# Sigfox_Featherwing-RP_SMA.net
KiCad netlist of a schematic drawn in EAGLE
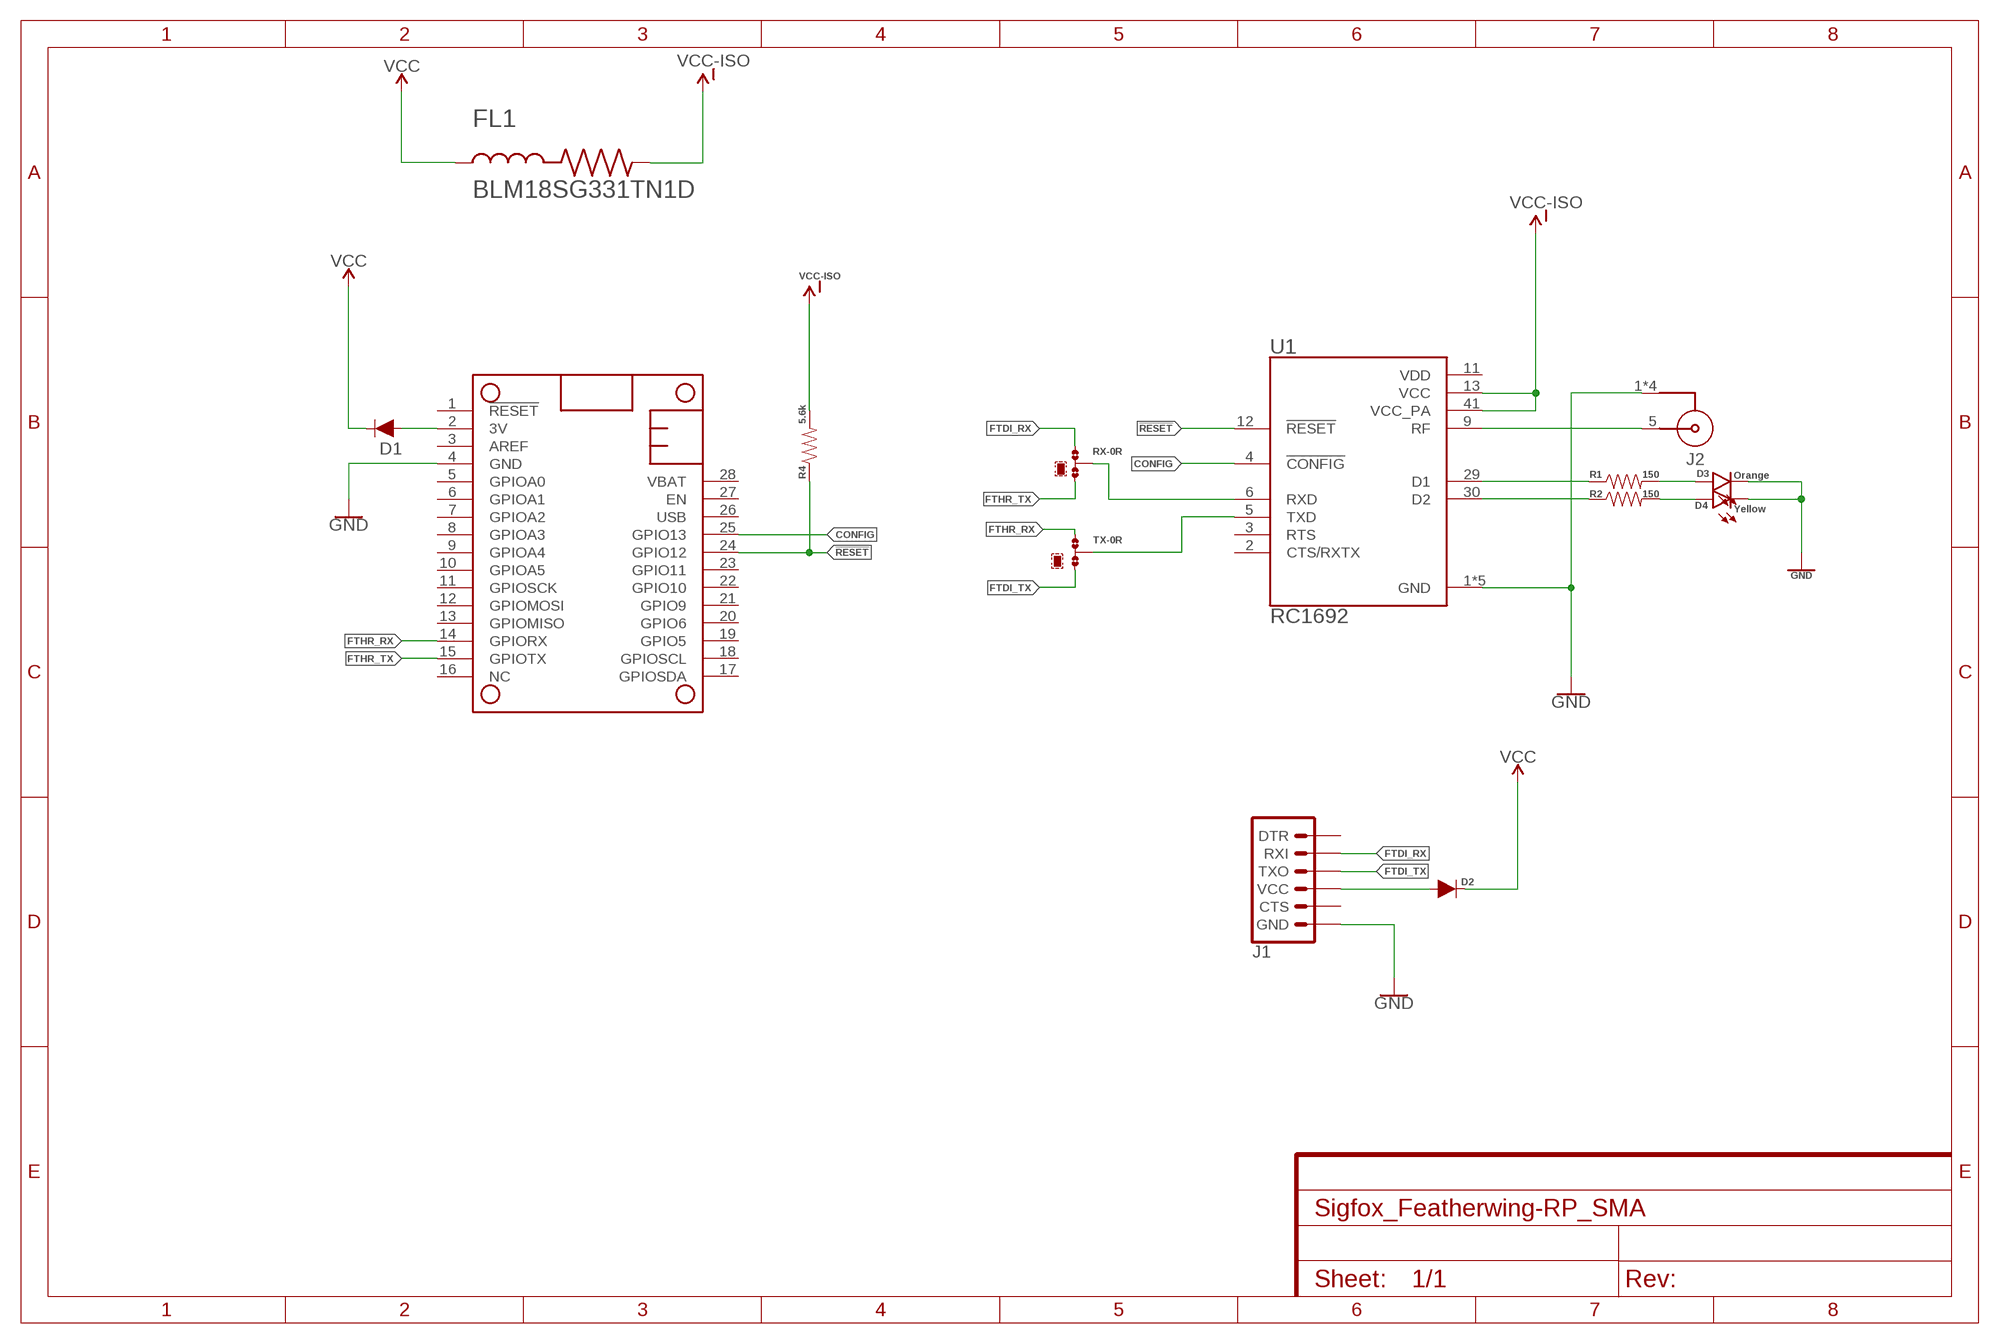
[diagram p0: schematic, sheet 1]

(export (version "E")
  (design (tool "Eeschema 10.0.6"))
  (components
    (comp (ref "D1")
      (value "250mA/100V")
      (footprint "eagle-import:SOD-323")
      (libsource (lib "eagle-import") (part "DIODE-BAS16J"))
    )
    (comp (ref "D2")
      (value "250mA/100V")
      (footprint "eagle-import:SOD-323")
      (libsource (lib "eagle-import") (part "DIODE-BAS16J"))
    )
    (comp (ref "D3")
      (value "Orange")
      (footprint "eagle-import:LED-0603")
      (libsource (lib "eagle-import") (part "LED-YELLOW0603"))
    )
    (comp (ref "D4")
      (value "Yellow")
      (footprint "eagle-import:LED-0603")
      (libsource (lib "eagle-import") (part "LED-YELLOW0603"))
    )
    (comp (ref "FL1")
      (value "BLM18SG331TN1D")
      (footprint "eagle-import:BEADC1608X65N")
      (fields (field (name "MF") "Murata Electronics"))
      (libsource (lib "eagle-import") (part "BLM18SG331TN1D"))
    )
    (comp (ref "J1")
      (value "6_PIN_SERIAL_TARGETSILK")
      (footprint "eagle-import:6_PIN_SERIAL_TARGET_SIDE_W_SILK")
      (libsource (lib "eagle-import") (part "6_PIN_SERIAL_TARGETSILK"))
    )
    (comp (ref "J2")
      (value "63012002124503")
      (footprint "eagle-import:63012002124503")
      (fields
        (field (name "DIGI-KEY_PART_NUMBER") "732-13860-ND")
        (field (name "MF") "Wurth Electronics Inc.")
      )
      (libsource (lib "eagle-import") (part "63012002124503"))
    )
    (comp (ref "MS1")
      (value "FEATHERWING")
      (footprint "eagle-import:FEATHERWING")
      (libsource (lib "eagle-import") (part "FEATHERWING"))
    )
    (comp (ref "R1")
      (value "150")
      (footprint "eagle-import:0603")
      (libsource (lib "eagle-import") (part "150OHM-0603-1/10W-1%"))
    )
    (comp (ref "R2")
      (value "150")
      (footprint "eagle-import:0603")
      (libsource (lib "eagle-import") (part "150OHM-0603-1/10W-1%"))
    )
    (comp (ref "R4")
      (value "5.6k")
      (footprint "eagle-import:0603")
      (libsource (lib "eagle-import") (part "5.6KOHM-0603-1/10W-1%"))
    )
    (comp (ref "RX")
      (value "0R-JUMPB")
      (footprint "eagle-import:B0R-JMP")
      (libsource (lib "eagle-import") (part "0R-JUMPB"))
    )
    (comp (ref "TX")
      (value "0R-JUMPB")
      (footprint "eagle-import:B0R-JMP")
      (libsource (lib "eagle-import") (part "0R-JUMPB"))
    )
    (comp (ref "U1")
      (value "RC1692")
      (footprint "eagle-import:MODULE_RC1682-SIG")
      (fields (field (name "MF") "Radiocrafts AS") (field (name "MP") "RC1682-SIG"))
      (libsource (lib "eagle-import") (part "RC1692"))
    )
  )
  (nets
    (net (code "1") (name "/USB") (class "Default")
      (node (ref "MS1") (pin "26") (pinfunction "USB_26") (pintype "power_in"))
    )
    (net (code "2") (name "/VBAT") (class "Default")
      (node (ref "MS1") (pin "28") (pinfunction "VBAT_28") (pintype "power_in"))
    )
    (net (code "3") (name "/VDD") (class "Default")
      (node (ref "U1") (pin "11") (pinfunction "VDD_11") (pintype "power_in"))
    )
    (net (code "4") (name "/~{RESET}") (class "Default")
      (node (ref "MS1") (pin "24") (pinfunction "GPIO12_24") (pintype "bidirectional"))
      (node (ref "R4") (pin "1") (pinfunction "1_1") (pintype "passive"))
      (node (ref "U1") (pin "12") (pinfunction "~{RESET}_12") (pintype "input"))
    )
    (net (code "5") (name "CONFIG") (class "Default")
      (node (ref "MS1") (pin "25") (pinfunction "GPIO13_25") (pintype "bidirectional"))
      (node (ref "U1") (pin "4") (pinfunction "~{CONFIG}_4") (pintype "input"))
    )
    (net (code "6") (name "FTDI_RX") (class "Default")
      (node (ref "J1") (pin "P$3") (pinfunction "RXI_P$3") (pintype "passive"))
      (node (ref "RX") (pin "1") (pinfunction "1_1") (pintype "passive"))
    )
    (net (code "7") (name "FTDI_TX") (class "Default")
      (node (ref "J1") (pin "P$2") (pinfunction "TXO_P$2") (pintype "passive"))
      (node (ref "TX") (pin "3") (pinfunction "3_3") (pintype "passive"))
    )
    (net (code "8") (name "FTHR_RX") (class "Default")
      (node (ref "MS1") (pin "14") (pinfunction "GPIORX_14") (pintype "bidirectional"))
      (node (ref "TX") (pin "1") (pinfunction "1_1") (pintype "passive"))
    )
    (net (code "9") (name "FTHR_TX") (class "Default")
      (node (ref "MS1") (pin "15") (pinfunction "GPIOTX_15") (pintype "bidirectional"))
      (node (ref "RX") (pin "3") (pinfunction "3_3") (pintype "passive"))
    )
    (net (code "10") (name "GND") (class "Default")
      (node (ref "D3") (pin "C") (pinfunction "C_C") (pintype "passive"))
      (node (ref "D4") (pin "C") (pinfunction "C_C") (pintype "passive"))
      (node (ref "J1") (pin "P$6") (pinfunction "GND_P$6") (pintype "passive"))
      (node (ref "J2") (pin "1") (pinfunction "2_1") (pintype "passive"))
      (node (ref "J2") (pin "2") (pinfunction "2_2") (pintype "passive"))
      (node (ref "J2") (pin "3") (pinfunction "2_3") (pintype "passive"))
      (node (ref "J2") (pin "4") (pinfunction "2_4") (pintype "passive"))
      (node (ref "MS1") (pin "4") (pinfunction "GND_4") (pintype "power_in"))
      (node (ref "U1") (pin "1") (pinfunction "GND_1") (pintype "power_in"))
      (node (ref "U1") (pin "10") (pinfunction "GND_10") (pintype "power_in"))
      (node (ref "U1") (pin "14") (pinfunction "GND_14") (pintype "power_in"))
      (node (ref "U1") (pin "7") (pinfunction "GND_7") (pintype "power_in"))
      (node (ref "U1") (pin "8") (pinfunction "GND_8") (pintype "power_in"))
    )
    (net (code "11") (name "Net-(D3-PadA)") (class "Default")
      (node (ref "D3") (pin "A") (pinfunction "A_A") (pintype "passive"))
      (node (ref "R1") (pin "2") (pinfunction "2_2") (pintype "passive"))
    )
    (net (code "12") (name "Net-(D4-PadA)") (class "Default")
      (node (ref "D4") (pin "A") (pinfunction "A_A") (pintype "passive"))
      (node (ref "R2") (pin "2") (pinfunction "2_2") (pintype "passive"))
    )
    (net (code "13") (name "Net-(J1-VCC)") (class "Default")
      (node (ref "D2") (pin "A") (pinfunction "A_A") (pintype "passive"))
      (node (ref "J1") (pin "P$4") (pinfunction "VCC_P$4") (pintype "passive"))
    )
    (net (code "14") (name "Net-(J2-1)") (class "Default")
      (node (ref "J2") (pin "5") (pinfunction "1_5") (pintype "passive"))
      (node (ref "U1") (pin "9") (pinfunction "RF_9") (pintype "bidirectional"))
    )
    (net (code "15") (name "Net-(MS1-3V)") (class "Default")
      (node (ref "D1") (pin "A") (pinfunction "A_A") (pintype "passive"))
      (node (ref "MS1") (pin "2") (pinfunction "3V_2") (pintype "power_in"))
    )
    (net (code "16") (name "Net-(U1-D1)") (class "Default")
      (node (ref "R1") (pin "1") (pinfunction "1_1") (pintype "passive"))
      (node (ref "U1") (pin "29") (pinfunction "D1_29") (pintype "bidirectional"))
    )
    (net (code "17") (name "Net-(U1-D2)") (class "Default")
      (node (ref "R2") (pin "1") (pinfunction "1_1") (pintype "passive"))
      (node (ref "U1") (pin "30") (pinfunction "D2_30") (pintype "bidirectional"))
    )
    (net (code "18") (name "Net-(U1-RXD)") (class "Default")
      (node (ref "RX") (pin "2") (pinfunction "2_2") (pintype "passive"))
      (node (ref "U1") (pin "6") (pinfunction "RXD_6") (pintype "input"))
    )
    (net (code "19") (name "Net-(U1-TXD)") (class "Default")
      (node (ref "TX") (pin "2") (pinfunction "2_2") (pintype "passive"))
      (node (ref "U1") (pin "5") (pinfunction "TXD_5") (pintype "output"))
    )
    (net (code "20") (name "VCC") (class "Default")
      (node (ref "D1") (pin "C") (pinfunction "C_C") (pintype "passive"))
      (node (ref "D2") (pin "C") (pinfunction "C_C") (pintype "passive"))
      (node (ref "FL1") (pin "1") (pinfunction "1_1") (pintype "passive"))
    )
    (net (code "21") (name "VCC-ISO") (class "Default")
      (node (ref "FL1") (pin "2") (pinfunction "2_2") (pintype "passive"))
      (node (ref "R4") (pin "2") (pinfunction "2_2") (pintype "passive"))
      (node (ref "U1") (pin "13") (pinfunction "VCC_13") (pintype "power_in"))
      (node (ref "U1") (pin "41") (pinfunction "VCC_PA_41") (pintype "power_in"))
    )
    (net (code "22") (name "unconnected-(J1-CTS-PadP$5)") (class "Default")
      (node (ref "J1") (pin "P$5") (pinfunction "CTS_P$5") (pintype "passive"))
    )
    (net (code "23") (name "unconnected-(J1-DTR-PadP$1)") (class "Default")
      (node (ref "J1") (pin "P$1") (pinfunction "DTR_P$1") (pintype "passive"))
    )
    (net (code "24") (name "unconnected-(MS1-AREF-Pad3)") (class "Default")
      (node (ref "MS1") (pin "3") (pinfunction "AREF_3") (pintype "passive"))
    )
    (net (code "25") (name "unconnected-(MS1-EN-Pad27)") (class "Default")
      (node (ref "MS1") (pin "27") (pinfunction "EN_27") (pintype "passive"))
    )
    (net (code "26") (name "unconnected-(MS1-GPIO5-Pad19)") (class "Default")
      (node (ref "MS1") (pin "19") (pinfunction "GPIO5_19") (pintype "bidirectional"))
    )
    (net (code "27") (name "unconnected-(MS1-GPIO6-Pad20)") (class "Default")
      (node (ref "MS1") (pin "20") (pinfunction "GPIO6_20") (pintype "bidirectional"))
    )
    (net (code "28") (name "unconnected-(MS1-GPIO9-Pad21)") (class "Default")
      (node (ref "MS1") (pin "21") (pinfunction "GPIO9_21") (pintype "bidirectional"))
    )
    (net (code "29") (name "unconnected-(MS1-GPIO10-Pad22)") (class "Default")
      (node (ref "MS1") (pin "22") (pinfunction "GPIO10_22") (pintype "bidirectional"))
    )
    (net (code "30") (name "unconnected-(MS1-GPIO11-Pad23)") (class "Default")
      (node (ref "MS1") (pin "23") (pinfunction "GPIO11_23") (pintype "bidirectional"))
    )
    (net (code "31") (name "unconnected-(MS1-GPIOA0-Pad5)") (class "Default")
      (node (ref "MS1") (pin "5") (pinfunction "GPIOA0_5") (pintype "bidirectional"))
    )
    (net (code "32") (name "unconnected-(MS1-GPIOA1-Pad6)") (class "Default")
      (node (ref "MS1") (pin "6") (pinfunction "GPIOA1_6") (pintype "bidirectional"))
    )
    (net (code "33") (name "unconnected-(MS1-GPIOA2-Pad7)") (class "Default")
      (node (ref "MS1") (pin "7") (pinfunction "GPIOA2_7") (pintype "bidirectional"))
    )
    (net (code "34") (name "unconnected-(MS1-GPIOA3-Pad8)") (class "Default")
      (node (ref "MS1") (pin "8") (pinfunction "GPIOA3_8") (pintype "bidirectional"))
    )
    (net (code "35") (name "unconnected-(MS1-GPIOA4-Pad9)") (class "Default")
      (node (ref "MS1") (pin "9") (pinfunction "GPIOA4_9") (pintype "bidirectional"))
    )
    (net (code "36") (name "unconnected-(MS1-GPIOA5-Pad10)") (class "Default")
      (node (ref "MS1") (pin "10") (pinfunction "GPIOA5_10") (pintype "bidirectional"))
    )
    (net (code "37") (name "unconnected-(MS1-GPIOMISO-Pad13)") (class "Default")
      (node (ref "MS1") (pin "13") (pinfunction "GPIOMISO_13") (pintype "bidirectional"))
    )
    (net (code "38") (name "unconnected-(MS1-GPIOMOSI-Pad12)") (class "Default")
      (node (ref "MS1") (pin "12") (pinfunction "GPIOMOSI_12") (pintype "bidirectional"))
    )
    (net (code "39") (name "unconnected-(MS1-GPIOSCK-Pad11)") (class "Default")
      (node (ref "MS1") (pin "11") (pinfunction "GPIOSCK_11") (pintype "bidirectional"))
    )
    (net (code "40") (name "unconnected-(MS1-GPIOSCL-Pad18)") (class "Default")
      (node (ref "MS1") (pin "18") (pinfunction "GPIOSCL_18") (pintype "bidirectional"))
    )
    (net (code "41") (name "unconnected-(MS1-GPIOSDA-Pad17)") (class "Default")
      (node (ref "MS1") (pin "17") (pinfunction "GPIOSDA_17") (pintype "bidirectional"))
    )
    (net (code "42") (name "unconnected-(MS1-NC-Pad16)") (class "Default")
      (node (ref "MS1") (pin "16") (pinfunction "NC_16") (pintype "passive"))
    )
    (net (code "43") (name "unconnected-(MS1-~{RESET}-Pad1)") (class "Default")
      (node (ref "MS1") (pin "1") (pinfunction "~{RESET}_1") (pintype "input"))
    )
    (net (code "44") (name "unconnected-(U1-CTS{slash}RXTX-Pad2)") (class "Default")
      (node (ref "U1") (pin "2") (pinfunction "CTS/RXTX_2") (pintype "bidirectional"))
    )
    (net (code "45") (name "unconnected-(U1-RTS-Pad3)") (class "Default")
      (node (ref "U1") (pin "3") (pinfunction "RTS_3") (pintype "input"))
    )
  )
)
